# ArtroEnergy2_0.net
KiCad netlist of a schematic drawn in EAGLE
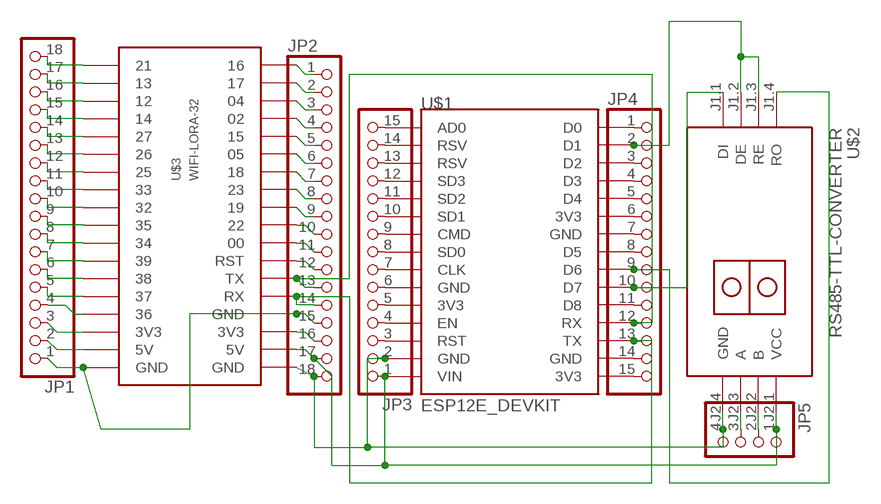
[diagram p0: schematic, sheet 1]

(export (version "E")
  (design (tool "Eeschema 10.0.6"))
  (components
    (comp (ref "JP1")
      (value "PINHD-1X18")
      (footprint "eagle-import:1X18")
      (libsource (lib "eagle-import") (part "PINHD-1X18"))
    )
    (comp (ref "JP2")
      (value "PINHD-1X18")
      (footprint "eagle-import:1X18")
      (libsource (lib "eagle-import") (part "PINHD-1X18"))
    )
    (comp (ref "JP3")
      (value "PINHD-1X15")
      (footprint "eagle-import:1X15")
      (libsource (lib "eagle-import") (part "PINHD-1X15"))
    )
    (comp (ref "JP4")
      (value "PINHD-1X15")
      (footprint "eagle-import:1X15")
      (libsource (lib "eagle-import") (part "PINHD-1X15"))
    )
    (comp (ref "JP5")
      (value "PINHD-1X4")
      (footprint "eagle-import:1X04")
      (libsource (lib "eagle-import") (part "PINHD-1X4"))
    )
    (comp (ref "U$1")
      (value "ESP12E_DEVKIT")
      (footprint "eagle-import:ESP12E_DEVKIT")
      (libsource (lib "eagle-import") (part "ESP12E_DEVKIT"))
    )
    (comp (ref "U$2")
      (value "RS485-TTL-CONVERTER")
      (footprint "eagle-import:RS485-TTL-CONVERTER")
      (libsource (lib "eagle-import") (part "RS485-TTL-CONVERTER"))
    )
    (comp (ref "U$3")
      (value "WIFI-LORA-32")
      (footprint "eagle-import:2.54MM_2X18")
      (libsource (lib "eagle-import") (part "WIFI-LORA-32"))
    )
  )
  (nets
    (net (code "1") (name "Net-(JP1-Pad1)") (class "Default")
      (node (ref "JP1") (pin "1") (pinfunction "1_1") (pintype "passive"))
      (node (ref "JP2") (pin "15") (pinfunction "15_15") (pintype "passive"))
      (node (ref "U$3") (pin "P$36") (pinfunction "GND_P$36") (pintype "power_in"))
      (node (ref "U$3") (pin "P$4") (pinfunction "GND_P$4") (pintype "bidirectional"))
    )
    (net (code "2") (name "Net-(JP1-Pad2)") (class "Default")
      (node (ref "JP1") (pin "2") (pinfunction "2_2") (pintype "passive"))
      (node (ref "U$3") (pin "P$35") (pinfunction "5V_P$35") (pintype "power_in"))
    )
    (net (code "3") (name "Net-(JP1-Pad3)") (class "Default")
      (node (ref "JP1") (pin "3") (pinfunction "3_3") (pintype "passive"))
      (node (ref "U$3") (pin "P$34") (pinfunction "3V3_P$34") (pintype "power_in"))
    )
    (net (code "4") (name "Net-(JP2-Pad16)") (class "Default")
      (node (ref "JP2") (pin "16") (pinfunction "16_16") (pintype "passive"))
      (node (ref "U$3") (pin "P$3") (pinfunction "3V3_P$3") (pintype "power_in"))
    )
    (net (code "5") (name "Net-(JP3-Pad3)") (class "Default")
      (node (ref "JP3") (pin "3") (pinfunction "3_3") (pintype "passive"))
      (node (ref "U$1") (pin "RST") (pinfunction "RST_RST") (pintype "bidirectional"))
    )
    (net (code "6") (name "Net-(JP3-Pad4)") (class "Default")
      (node (ref "JP3") (pin "4") (pinfunction "4_4") (pintype "passive"))
      (node (ref "U$1") (pin "EN") (pinfunction "EN_EN") (pintype "bidirectional"))
    )
    (net (code "7") (name "Net-(JP3-Pad5)") (class "Default")
      (node (ref "JP3") (pin "5") (pinfunction "5_5") (pintype "passive"))
      (node (ref "U$1") (pin "3V3@0") (pinfunction "3V3_3V3@0") (pintype "bidirectional"))
    )
    (net (code "8") (name "Net-(JP3-Pad6)") (class "Default")
      (node (ref "JP3") (pin "6") (pinfunction "6_6") (pintype "passive"))
      (node (ref "U$1") (pin "GND@0") (pinfunction "GND_GND@0") (pintype "bidirectional"))
    )
    (net (code "9") (name "Net-(JP3-Pad7)") (class "Default")
      (node (ref "JP3") (pin "7") (pinfunction "7_7") (pintype "passive"))
      (node (ref "U$1") (pin "CLK") (pinfunction "CLK_CLK") (pintype "bidirectional"))
    )
    (net (code "10") (name "Net-(JP3-Pad8)") (class "Default")
      (node (ref "JP3") (pin "8") (pinfunction "8_8") (pintype "passive"))
      (node (ref "U$1") (pin "SD0") (pinfunction "SD0_SD0") (pintype "bidirectional"))
    )
    (net (code "11") (name "Net-(JP3-Pad9)") (class "Default")
      (node (ref "JP3") (pin "9") (pinfunction "9_9") (pintype "passive"))
      (node (ref "U$1") (pin "CMD") (pinfunction "CMD_CMD") (pintype "bidirectional"))
    )
    (net (code "12") (name "Net-(JP3-Pad10)") (class "Default")
      (node (ref "JP3") (pin "10") (pinfunction "10_10") (pintype "passive"))
      (node (ref "U$1") (pin "SD1") (pinfunction "SD1_SD1") (pintype "bidirectional"))
    )
    (net (code "13") (name "Net-(JP3-Pad11)") (class "Default")
      (node (ref "JP3") (pin "11") (pinfunction "11_11") (pintype "passive"))
      (node (ref "U$1") (pin "SD2") (pinfunction "SD2_SD2") (pintype "bidirectional"))
    )
    (net (code "14") (name "Net-(JP3-Pad12)") (class "Default")
      (node (ref "JP3") (pin "12") (pinfunction "12_12") (pintype "passive"))
      (node (ref "U$1") (pin "SD3") (pinfunction "SD3_SD3") (pintype "bidirectional"))
    )
    (net (code "15") (name "Net-(JP3-Pad13)") (class "Default")
      (node (ref "JP3") (pin "13") (pinfunction "13_13") (pintype "passive"))
      (node (ref "U$1") (pin "RSV@1") (pinfunction "RSV_RSV@1") (pintype "bidirectional"))
    )
    (net (code "16") (name "Net-(JP3-Pad14)") (class "Default")
      (node (ref "JP3") (pin "14") (pinfunction "14_14") (pintype "passive"))
      (node (ref "U$1") (pin "RSV@0") (pinfunction "RSV_RSV@0") (pintype "bidirectional"))
    )
    (net (code "17") (name "Net-(JP3-Pad15)") (class "Default")
      (node (ref "JP3") (pin "15") (pinfunction "15_15") (pintype "passive"))
      (node (ref "U$1") (pin "AD0") (pinfunction "AD0_AD0") (pintype "bidirectional"))
    )
    (net (code "18") (name "Net-(JP4-Pad1)") (class "Default")
      (node (ref "JP4") (pin "1") (pinfunction "1_1") (pintype "passive"))
      (node (ref "U$1") (pin "D0") (pinfunction "D0_D0") (pintype "bidirectional"))
    )
    (net (code "19") (name "Net-(JP4-Pad3)") (class "Default")
      (node (ref "JP4") (pin "3") (pinfunction "3_3") (pintype "passive"))
      (node (ref "U$1") (pin "D2") (pinfunction "D2_D2") (pintype "bidirectional"))
    )
    (net (code "20") (name "Net-(JP4-Pad4)") (class "Default")
      (node (ref "JP4") (pin "4") (pinfunction "4_4") (pintype "passive"))
      (node (ref "U$1") (pin "D3") (pinfunction "D3_D3") (pintype "bidirectional"))
    )
    (net (code "21") (name "Net-(JP4-Pad5)") (class "Default")
      (node (ref "JP4") (pin "5") (pinfunction "5_5") (pintype "passive"))
      (node (ref "U$1") (pin "D4") (pinfunction "D4_D4") (pintype "bidirectional"))
    )
    (net (code "22") (name "Net-(JP4-Pad6)") (class "Default")
      (node (ref "JP4") (pin "6") (pinfunction "6_6") (pintype "passive"))
      (node (ref "U$1") (pin "3V3@1") (pinfunction "3V3_3V3@1") (pintype "bidirectional"))
    )
    (net (code "23") (name "Net-(JP4-Pad7)") (class "Default")
      (node (ref "JP4") (pin "7") (pinfunction "7_7") (pintype "passive"))
      (node (ref "U$1") (pin "GND@2") (pinfunction "GND_GND@2") (pintype "bidirectional"))
    )
    (net (code "24") (name "Net-(JP4-Pad8)") (class "Default")
      (node (ref "JP4") (pin "8") (pinfunction "8_8") (pintype "passive"))
      (node (ref "U$1") (pin "D5") (pinfunction "D5_D5") (pintype "bidirectional"))
    )
    (net (code "25") (name "Net-(JP4-Pad11)") (class "Default")
      (node (ref "JP4") (pin "11") (pinfunction "11_11") (pintype "passive"))
      (node (ref "U$1") (pin "D8") (pinfunction "D8_D8") (pintype "bidirectional"))
    )
    (net (code "26") (name "Net-(JP4-Pad14)") (class "Default")
      (node (ref "JP4") (pin "14") (pinfunction "14_14") (pintype "passive"))
      (node (ref "U$1") (pin "GND@3") (pinfunction "GND_GND@3") (pintype "bidirectional"))
    )
    (net (code "27") (name "Net-(JP4-Pad15)") (class "Default")
      (node (ref "JP4") (pin "15") (pinfunction "15_15") (pintype "passive"))
      (node (ref "U$1") (pin "3V3@2") (pinfunction "3V3_3V3@2") (pintype "bidirectional"))
    )
    (net (code "28") (name "Net-(U$2-A)") (class "Default")
      (node (ref "JP5") (pin "3") (pinfunction "3_3") (pintype "passive"))
      (node (ref "U$2") (pin "J2.3") (pinfunction "A_J2.3") (pintype "passive"))
    )
    (net (code "29") (name "Net-(U$2-B)") (class "Default")
      (node (ref "JP5") (pin "2") (pinfunction "2_2") (pintype "passive"))
      (node (ref "U$2") (pin "J2.2") (pinfunction "B_J2.2") (pintype "passive"))
    )
    (net (code "30") (name "Net-(U$2-DE)") (class "Default")
      (node (ref "JP4") (pin "2") (pinfunction "2_2") (pintype "passive"))
      (node (ref "U$1") (pin "D1") (pinfunction "D1_D1") (pintype "bidirectional"))
      (node (ref "U$2") (pin "J1.2") (pinfunction "DE_J1.2") (pintype "passive"))
      (node (ref "U$2") (pin "J1.3") (pinfunction "RE_J1.3") (pintype "passive"))
    )
    (net (code "31") (name "Net-(U$2-DI)") (class "Default")
      (node (ref "JP4") (pin "10") (pinfunction "10_10") (pintype "passive"))
      (node (ref "U$1") (pin "D7") (pinfunction "D7_D7") (pintype "bidirectional"))
      (node (ref "U$2") (pin "J1.1") (pinfunction "DI_J1.1") (pintype "passive"))
    )
    (net (code "32") (name "Net-(U$2-GND)") (class "Default")
      (node (ref "JP2") (pin "18") (pinfunction "18_18") (pintype "passive"))
      (node (ref "JP3") (pin "2") (pinfunction "2_2") (pintype "passive"))
      (node (ref "JP5") (pin "4") (pinfunction "4_4") (pintype "passive"))
      (node (ref "U$1") (pin "GND@1") (pinfunction "GND_GND@1") (pintype "bidirectional"))
      (node (ref "U$2") (pin "J2.4") (pinfunction "GND_J2.4") (pintype "power_in"))
      (node (ref "U$3") (pin "P$1") (pinfunction "GND_P$1") (pintype "power_in"))
    )
    (net (code "33") (name "Net-(U$2-RO)") (class "Default")
      (node (ref "JP4") (pin "9") (pinfunction "9_9") (pintype "passive"))
      (node (ref "U$1") (pin "D6") (pinfunction "D6_D6") (pintype "bidirectional"))
      (node (ref "U$2") (pin "J1.4") (pinfunction "RO_J1.4") (pintype "passive"))
    )
    (net (code "34") (name "Net-(U$2-VCC)") (class "Default")
      (node (ref "JP2") (pin "17") (pinfunction "17_17") (pintype "passive"))
      (node (ref "JP3") (pin "1") (pinfunction "1_1") (pintype "passive"))
      (node (ref "JP5") (pin "1") (pinfunction "1_1") (pintype "passive"))
      (node (ref "U$1") (pin "VIN") (pinfunction "VIN_VIN") (pintype "bidirectional"))
      (node (ref "U$2") (pin "J2.1") (pinfunction "VCC_J2.1") (pintype "power_in"))
      (node (ref "U$3") (pin "P$2") (pinfunction "5V_P$2") (pintype "power_in"))
    )
    (net (code "35") (name "Net-(U$3-00)") (class "Default")
      (node (ref "JP2") (pin "11") (pinfunction "11_11") (pintype "passive"))
      (node (ref "U$3") (pin "P$8") (pinfunction "00_P$8") (pintype "bidirectional"))
    )
    (net (code "36") (name "Net-(U$3-02)") (class "Default")
      (node (ref "JP2") (pin "4") (pinfunction "4_4") (pintype "passive"))
      (node (ref "U$3") (pin "P$15") (pinfunction "02_P$15") (pintype "bidirectional"))
    )
    (net (code "37") (name "Net-(U$3-04)") (class "Default")
      (node (ref "JP2") (pin "3") (pinfunction "3_3") (pintype "passive"))
      (node (ref "U$3") (pin "P$16") (pinfunction "04_P$16") (pintype "bidirectional"))
    )
    (net (code "38") (name "Net-(U$3-05)") (class "Default")
      (node (ref "JP2") (pin "6") (pinfunction "6_6") (pintype "passive"))
      (node (ref "U$3") (pin "P$13") (pinfunction "05_P$13") (pintype "bidirectional"))
    )
    (net (code "39") (name "Net-(U$3-12)") (class "Default")
      (node (ref "JP1") (pin "16") (pinfunction "16_16") (pintype "passive"))
      (node (ref "U$3") (pin "P$21") (pinfunction "12_P$21") (pintype "bidirectional"))
    )
    (net (code "40") (name "Net-(U$3-13)") (class "Default")
      (node (ref "JP1") (pin "17") (pinfunction "17_17") (pintype "passive"))
      (node (ref "U$3") (pin "P$20") (pinfunction "13_P$20") (pintype "bidirectional"))
    )
    (net (code "41") (name "Net-(U$3-14)") (class "Default")
      (node (ref "JP1") (pin "15") (pinfunction "15_15") (pintype "passive"))
      (node (ref "U$3") (pin "P$22") (pinfunction "14_P$22") (pintype "bidirectional"))
    )
    (net (code "42") (name "Net-(U$3-15)") (class "Default")
      (node (ref "JP2") (pin "5") (pinfunction "5_5") (pintype "passive"))
      (node (ref "U$3") (pin "P$14") (pinfunction "15_P$14") (pintype "bidirectional"))
    )
    (net (code "43") (name "Net-(U$3-16)") (class "Default")
      (node (ref "JP2") (pin "1") (pinfunction "1_1") (pintype "passive"))
      (node (ref "U$3") (pin "P$18") (pinfunction "16_P$18") (pintype "bidirectional"))
    )
    (net (code "44") (name "Net-(U$3-17)") (class "Default")
      (node (ref "JP2") (pin "2") (pinfunction "2_2") (pintype "passive"))
      (node (ref "U$3") (pin "P$17") (pinfunction "17_P$17") (pintype "bidirectional"))
    )
    (net (code "45") (name "Net-(U$3-18)") (class "Default")
      (node (ref "JP2") (pin "7") (pinfunction "7_7") (pintype "passive"))
      (node (ref "U$3") (pin "P$12") (pinfunction "18_P$12") (pintype "bidirectional"))
    )
    (net (code "46") (name "Net-(U$3-19)") (class "Default")
      (node (ref "JP2") (pin "9") (pinfunction "9_9") (pintype "passive"))
      (node (ref "U$3") (pin "P$10") (pinfunction "19_P$10") (pintype "bidirectional"))
    )
    (net (code "47") (name "Net-(U$3-21)") (class "Default")
      (node (ref "JP1") (pin "18") (pinfunction "18_18") (pintype "passive"))
      (node (ref "U$3") (pin "P$19") (pinfunction "21_P$19") (pintype "bidirectional"))
    )
    (net (code "48") (name "Net-(U$3-22)") (class "Default")
      (node (ref "JP2") (pin "10") (pinfunction "10_10") (pintype "passive"))
      (node (ref "U$3") (pin "P$9") (pinfunction "22_P$9") (pintype "bidirectional"))
    )
    (net (code "49") (name "Net-(U$3-23)") (class "Default")
      (node (ref "JP2") (pin "8") (pinfunction "8_8") (pintype "passive"))
      (node (ref "U$3") (pin "P$11") (pinfunction "23_P$11") (pintype "bidirectional"))
    )
    (net (code "50") (name "Net-(U$3-25)") (class "Default")
      (node (ref "JP1") (pin "12") (pinfunction "12_12") (pintype "passive"))
      (node (ref "U$3") (pin "P$25") (pinfunction "25_P$25") (pintype "bidirectional"))
    )
    (net (code "51") (name "Net-(U$3-26)") (class "Default")
      (node (ref "JP1") (pin "13") (pinfunction "13_13") (pintype "passive"))
      (node (ref "U$3") (pin "P$24") (pinfunction "26_P$24") (pintype "bidirectional"))
    )
    (net (code "52") (name "Net-(U$3-27)") (class "Default")
      (node (ref "JP1") (pin "14") (pinfunction "14_14") (pintype "passive"))
      (node (ref "U$3") (pin "P$23") (pinfunction "27_P$23") (pintype "bidirectional"))
    )
    (net (code "53") (name "Net-(U$3-32)") (class "Default")
      (node (ref "JP1") (pin "10") (pinfunction "10_10") (pintype "passive"))
      (node (ref "U$3") (pin "P$27") (pinfunction "32_P$27") (pintype "bidirectional"))
    )
    (net (code "54") (name "Net-(U$3-33)") (class "Default")
      (node (ref "JP1") (pin "11") (pinfunction "11_11") (pintype "passive"))
      (node (ref "U$3") (pin "P$26") (pinfunction "33_P$26") (pintype "bidirectional"))
    )
    (net (code "55") (name "Net-(U$3-34)") (class "Default")
      (node (ref "JP1") (pin "8") (pinfunction "8_8") (pintype "passive"))
      (node (ref "U$3") (pin "P$29") (pinfunction "34_P$29") (pintype "bidirectional"))
    )
    (net (code "56") (name "Net-(U$3-35)") (class "Default")
      (node (ref "JP1") (pin "9") (pinfunction "9_9") (pintype "passive"))
      (node (ref "U$3") (pin "P$28") (pinfunction "35_P$28") (pintype "bidirectional"))
    )
    (net (code "57") (name "Net-(U$3-36)") (class "Default")
      (node (ref "JP1") (pin "4") (pinfunction "4_4") (pintype "passive"))
      (node (ref "U$3") (pin "P$33") (pinfunction "36_P$33") (pintype "bidirectional"))
    )
    (net (code "58") (name "Net-(U$3-37)") (class "Default")
      (node (ref "JP1") (pin "5") (pinfunction "5_5") (pintype "passive"))
      (node (ref "U$3") (pin "P$32") (pinfunction "37_P$32") (pintype "bidirectional"))
    )
    (net (code "59") (name "Net-(U$3-38)") (class "Default")
      (node (ref "JP1") (pin "6") (pinfunction "6_6") (pintype "passive"))
      (node (ref "U$3") (pin "P$31") (pinfunction "38_P$31") (pintype "bidirectional"))
    )
    (net (code "60") (name "Net-(U$3-39)") (class "Default")
      (node (ref "JP1") (pin "7") (pinfunction "7_7") (pintype "passive"))
      (node (ref "U$3") (pin "P$30") (pinfunction "39_P$30") (pintype "bidirectional"))
    )
    (net (code "61") (name "Net-(U$3-RST)") (class "Default")
      (node (ref "JP2") (pin "12") (pinfunction "12_12") (pintype "passive"))
      (node (ref "U$3") (pin "P$7") (pinfunction "RST_P$7") (pintype "bidirectional"))
    )
    (net (code "62") (name "Net-(U$3-RX)") (class "Default")
      (node (ref "JP2") (pin "14") (pinfunction "14_14") (pintype "passive"))
      (node (ref "JP4") (pin "13") (pinfunction "13_13") (pintype "passive"))
      (node (ref "U$1") (pin "TX") (pinfunction "TX_TX") (pintype "bidirectional"))
      (node (ref "U$3") (pin "P$5") (pinfunction "RX_P$5") (pintype "bidirectional"))
    )
    (net (code "63") (name "Net-(U$3-TX)") (class "Default")
      (node (ref "JP2") (pin "13") (pinfunction "13_13") (pintype "passive"))
      (node (ref "JP4") (pin "12") (pinfunction "12_12") (pintype "passive"))
      (node (ref "U$1") (pin "RX") (pinfunction "RX_RX") (pintype "bidirectional"))
      (node (ref "U$3") (pin "P$6") (pinfunction "TX_P$6") (pintype "bidirectional"))
    )
  )
)
